# Shield_v1.net
KiCad netlist of a schematic drawn in EAGLE
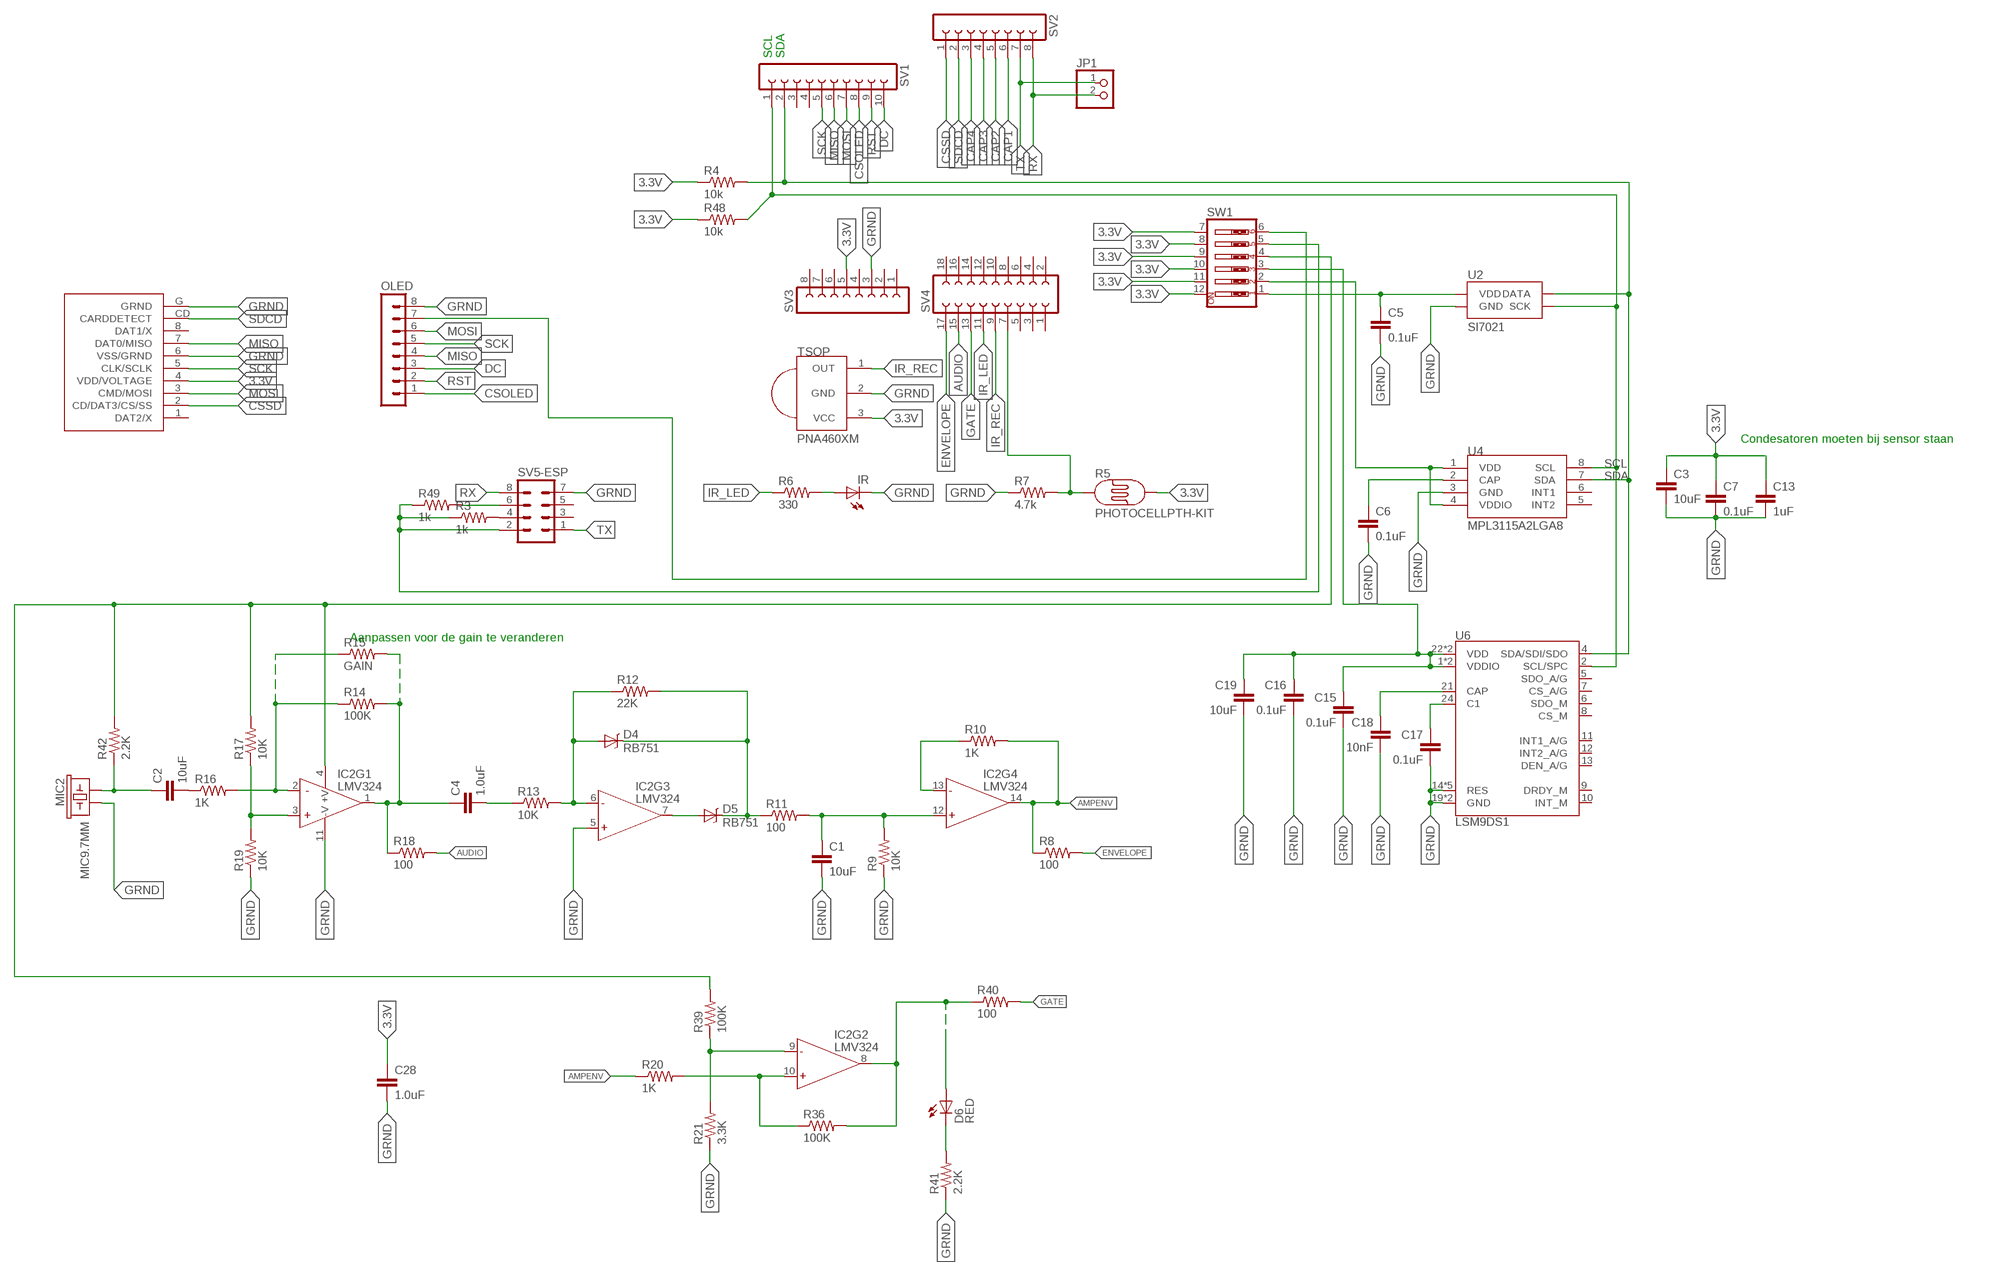
[diagram p0: schematic, sheet 1]

(export (version "E")
  (design (tool "Eeschema 10.0.6"))
  (components
    (comp (ref "C1")
      (value "10uF")
      (footprint "eagle-import:C1206")
      (libsource (lib "eagle-import") (part "C-EUC1206"))
    )
    (comp (ref "C2")
      (value "10uF")
      (footprint "eagle-import:C1206")
      (libsource (lib "eagle-import") (part "C-EUC1206"))
    )
    (comp (ref "C3")
      (value "10uF")
      (footprint "eagle-import:C1206")
      (libsource (lib "eagle-import") (part "C-EUC1206"))
    )
    (comp (ref "C4")
      (value "1.0uF")
      (footprint "eagle-import:C1206")
      (libsource (lib "eagle-import") (part "C-EUC1206"))
    )
    (comp (ref "C5")
      (value "0.1uF")
      (footprint "eagle-import:C1206")
      (libsource (lib "eagle-import") (part "C-EUC1206"))
    )
    (comp (ref "C6")
      (value "0.1uF")
      (footprint "eagle-import:C1206")
      (libsource (lib "eagle-import") (part "C-EUC1206"))
    )
    (comp (ref "C7")
      (value "0.1uF")
      (footprint "eagle-import:C1206")
      (libsource (lib "eagle-import") (part "C-EUC1206"))
    )
    (comp (ref "C13")
      (value "1uF")
      (footprint "eagle-import:C1206")
      (libsource (lib "eagle-import") (part "C-EUC1206"))
    )
    (comp (ref "C15")
      (value "0.1uF")
      (footprint "eagle-import:C1206")
      (libsource (lib "eagle-import") (part "C-EUC1206"))
    )
    (comp (ref "C16")
      (value "0.1uF")
      (footprint "eagle-import:C1206")
      (libsource (lib "eagle-import") (part "C-EUC1206"))
    )
    (comp (ref "C17")
      (value "0.1uF")
      (footprint "eagle-import:C1206")
      (libsource (lib "eagle-import") (part "C-EUC1206"))
    )
    (comp (ref "C18")
      (value "10nF")
      (footprint "eagle-import:C1206")
      (libsource (lib "eagle-import") (part "C-EUC1206"))
    )
    (comp (ref "C19")
      (value "10uF")
      (footprint "eagle-import:C1206")
      (libsource (lib "eagle-import") (part "C-EUC1206"))
    )
    (comp (ref "C28")
      (value "1.0uF")
      (footprint "eagle-import:C1206")
      (libsource (lib "eagle-import") (part "C-EUC1206"))
    )
    (comp (ref "D4")
      (value "RB751")
      (footprint "eagle-import:SOD-523")
      (libsource (lib "eagle-import") (part "RB751"))
    )
    (comp (ref "D5")
      (value "RB751")
      (footprint "eagle-import:SOD-523")
      (libsource (lib "eagle-import") (part "RB751"))
    )
    (comp (ref "D6")
      (value "RED")
      (footprint "eagle-import:LED3MM")
      (libsource (lib "eagle-import") (part "led_LED3MM"))
    )
    (comp (ref "IC2")
      (value "LMV324")
      (footprint "eagle-import:SO014")
      (libsource (lib "eagle-import") (part "LMV324"))
    )
    (comp (ref "IR")
      (value "LED5MM")
      (footprint "eagle-import:LED5MM")
      (libsource (lib "eagle-import") (part "LED5MM"))
    )
    (comp (ref "JP1")
      (value "PINHD-1X2")
      (footprint "eagle-import:1X02")
      (libsource (lib "eagle-import") (part "PINHD-1X2"))
    )
    (comp (ref "MIC2")
      (value "MIC9.7MM")
      (footprint "eagle-import:MIC-9.7MM")
      (libsource (lib "eagle-import") (part "MIC9.7MM"))
    )
    (comp (ref "OLED")
      (value "MA08-1")
      (footprint "eagle-import:MA08-1")
      (libsource (lib "eagle-import") (part "MA08-1"))
    )
    (comp (ref "R3")
      (value "1k")
      (footprint "eagle-import:R1206")
      (libsource (lib "eagle-import") (part "R-US_R1206"))
    )
    (comp (ref "R4")
      (value "10k")
      (footprint "eagle-import:R1206")
      (libsource (lib "eagle-import") (part "R-US_R1206"))
    )
    (comp (ref "R5")
      (value "PHOTOCELLPTH-KIT")
      (footprint "eagle-import:PHOTOCELL-KIT")
      (libsource (lib "eagle-import") (part "PHOTOCELLPTH-KIT"))
    )
    (comp (ref "R6")
      (value "330")
      (footprint "eagle-import:R1206")
      (libsource (lib "eagle-import") (part "R-US_R1206"))
    )
    (comp (ref "R7")
      (value "4.7k")
      (footprint "eagle-import:R1206")
      (libsource (lib "eagle-import") (part "R-US_R1206"))
    )
    (comp (ref "R8")
      (value "100")
      (footprint "eagle-import:R1206")
      (libsource (lib "eagle-import") (part "R-US_R1206"))
    )
    (comp (ref "R9")
      (value "10K")
      (footprint "eagle-import:R1206")
      (libsource (lib "eagle-import") (part "R-US_R1206"))
    )
    (comp (ref "R10")
      (value "1K")
      (footprint "eagle-import:R1206")
      (libsource (lib "eagle-import") (part "R-US_R1206"))
    )
    (comp (ref "R11")
      (value "100")
      (footprint "eagle-import:R1206")
      (libsource (lib "eagle-import") (part "R-US_R1206"))
    )
    (comp (ref "R12")
      (value "22K")
      (footprint "eagle-import:R1206")
      (libsource (lib "eagle-import") (part "R-US_R1206"))
    )
    (comp (ref "R13")
      (value "10K")
      (footprint "eagle-import:R1206")
      (libsource (lib "eagle-import") (part "R-US_R1206"))
    )
    (comp (ref "R14")
      (value "100K")
      (footprint "eagle-import:R1206")
      (libsource (lib "eagle-import") (part "R-US_R1206"))
    )
    (comp (ref "R15")
      (value "GAIN")
      (footprint "eagle-import:R1206")
      (libsource (lib "eagle-import") (part "R-US_R1206"))
    )
    (comp (ref "R16")
      (value "1K")
      (footprint "eagle-import:R1206")
      (libsource (lib "eagle-import") (part "R-US_R1206"))
    )
    (comp (ref "R17")
      (value "10K")
      (footprint "eagle-import:R1206")
      (libsource (lib "eagle-import") (part "R-US_R1206"))
    )
    (comp (ref "R18")
      (value "100")
      (footprint "eagle-import:R1206")
      (libsource (lib "eagle-import") (part "R-US_R1206"))
    )
    (comp (ref "R19")
      (value "10K")
      (footprint "eagle-import:R1206")
      (libsource (lib "eagle-import") (part "R-US_R1206"))
    )
    (comp (ref "R20")
      (value "1K")
      (footprint "eagle-import:R1206")
      (libsource (lib "eagle-import") (part "R-US_R1206"))
    )
    (comp (ref "R21")
      (value "3.3K")
      (footprint "eagle-import:R1206")
      (libsource (lib "eagle-import") (part "R-US_R1206"))
    )
    (comp (ref "R36")
      (value "100K")
      (footprint "eagle-import:R1206")
      (libsource (lib "eagle-import") (part "R-US_R1206"))
    )
    (comp (ref "R39")
      (value "100K")
      (footprint "eagle-import:R1206")
      (libsource (lib "eagle-import") (part "R-US_R1206"))
    )
    (comp (ref "R40")
      (value "100")
      (footprint "eagle-import:R1206")
      (libsource (lib "eagle-import") (part "R-US_R1206"))
    )
    (comp (ref "R41")
      (value "2.2K")
      (footprint "eagle-import:R1206")
      (libsource (lib "eagle-import") (part "R-US_R1206"))
    )
    (comp (ref "R42")
      (value "2.2K")
      (footprint "eagle-import:R1206")
      (libsource (lib "eagle-import") (part "R-US_R1206"))
    )
    (comp (ref "R48")
      (value "10k")
      (footprint "eagle-import:R1206")
      (libsource (lib "eagle-import") (part "R-US_R1206"))
    )
    (comp (ref "R49")
      (value "1k")
      (footprint "eagle-import:R1206")
      (libsource (lib "eagle-import") (part "R-US_R1206"))
    )
    (comp (ref "SV1")
      (value "FE10-1")
      (footprint "eagle-import:FE10")
      (libsource (lib "eagle-import") (part "FE10-1"))
    )
    (comp (ref "SV2")
      (value "FE08-1")
      (footprint "eagle-import:FE08")
      (libsource (lib "eagle-import") (part "FE08-1"))
    )
    (comp (ref "SV3")
      (value "FE08-1")
      (footprint "eagle-import:FE08")
      (libsource (lib "eagle-import") (part "FE08-1"))
    )
    (comp (ref "SV4")
      (value "FE09-2")
      (footprint "eagle-import:FE09-2")
      (libsource (lib "eagle-import") (part "FE09-2"))
    )
    (comp (ref "SV5-ESP")
      (value "MA04-2")
      (footprint "eagle-import:MA04-2")
      (libsource (lib "eagle-import") (part "MA04-2"))
    )
    (comp (ref "SW1")
      (value "SW_DIP-6")
      (footprint "eagle-import:EDG-06")
      (libsource (lib "eagle-import") (part "SW_DIP-6"))
    )
    (comp (ref "TSOP")
      (value "PNA460XM")
      (footprint "eagle-import:PNA460XM")
      (libsource (lib "eagle-import") (part "PNA460XM"))
    )
    (comp (ref "U$1")
      (value "SDCARD")
      (footprint "eagle-import:SD_CARD")
      (libsource (lib "eagle-import") (part "SDCARD"))
    )
    (comp (ref "U2")
      (value "SI7021")
      (footprint "eagle-import:SI7021")
      (libsource (lib "eagle-import") (part "SI7021"))
    )
    (comp (ref "U4")
      (value "MPL3115A2LGA8")
      (footprint "eagle-import:LGA8")
      (libsource (lib "eagle-import") (part "MPL3115A2LGA8"))
    )
    (comp (ref "U6")
      (value "LSM9DS1")
      (footprint "eagle-import:LGA24-8X4")
      (libsource (lib "eagle-import") (part "LSM9DS1"))
    )
  )
  (nets
    (net (code "1") (name "/SCL") (class "Default")
      (node (ref "R48") (pin "2") (pinfunction "2_2") (pintype "passive"))
      (node (ref "SV1") (pin "1") (pinfunction "1_1") (pintype "passive"))
      (node (ref "U2") (pin "SCK") (pinfunction "SCK_SCK") (pintype "input"))
      (node (ref "U4") (pin "8") (pinfunction "SCL_8") (pintype "bidirectional"))
      (node (ref "U6") (pin "2") (pinfunction "SCL/SPC_2") (pintype "bidirectional"))
    )
    (net (code "2") (name "/SDA") (class "Default")
      (node (ref "R4") (pin "2") (pinfunction "2_2") (pintype "passive"))
      (node (ref "SV1") (pin "2") (pinfunction "2_2") (pintype "passive"))
      (node (ref "U2") (pin "DATA") (pinfunction "DATA_DATA") (pintype "bidirectional"))
      (node (ref "U4") (pin "7") (pinfunction "SDA_7") (pintype "bidirectional"))
      (node (ref "U6") (pin "4") (pinfunction "SDA/SDI/SDO_4") (pintype "bidirectional"))
    )
    (net (code "3") (name "3.3V") (class "Default")
      (node (ref "C13") (pin "1") (pinfunction "1_1") (pintype "passive"))
      (node (ref "C28") (pin "1") (pinfunction "1_1") (pintype "passive"))
      (node (ref "C3") (pin "1") (pinfunction "1_1") (pintype "passive"))
      (node (ref "C7") (pin "1") (pinfunction "1_1") (pintype "passive"))
      (node (ref "R4") (pin "1") (pinfunction "1_1") (pintype "passive"))
      (node (ref "R48") (pin "1") (pinfunction "1_1") (pintype "passive"))
      (node (ref "R5") (pin "2") (pinfunction "P$2_2") (pintype "bidirectional"))
      (node (ref "SV3") (pin "5") (pinfunction "5_5") (pintype "passive"))
      (node (ref "SW1") (pin "10") (pinfunction "10_10") (pintype "passive"))
      (node (ref "SW1") (pin "11") (pinfunction "11_11") (pintype "passive"))
      (node (ref "SW1") (pin "12") (pinfunction "12_12") (pintype "passive"))
      (node (ref "SW1") (pin "7") (pinfunction "7_7") (pintype "passive"))
      (node (ref "SW1") (pin "8") (pinfunction "8_8") (pintype "passive"))
      (node (ref "SW1") (pin "9") (pinfunction "9_9") (pintype "passive"))
      (node (ref "TSOP") (pin "3") (pinfunction "VCC_3") (pintype "power_in"))
      (node (ref "U$1") (pin "4") (pinfunction "VDD/VOLTAGE_4") (pintype "bidirectional"))
    )
    (net (code "4") (name "AMPENV") (class "Default")
      (node (ref "IC2") (pin "14") (pinfunction "OUT_14") (pintype "output"))
      (node (ref "R10") (pin "2") (pinfunction "2_2") (pintype "passive"))
      (node (ref "R20") (pin "1") (pinfunction "1_1") (pintype "passive"))
      (node (ref "R8") (pin "1") (pinfunction "1_1") (pintype "passive"))
    )
    (net (code "5") (name "AUDIO") (class "Default")
      (node (ref "R18") (pin "2") (pinfunction "2_2") (pintype "passive"))
      (node (ref "R5") (pin "1") (pinfunction "P$1_1") (pintype "bidirectional"))
      (node (ref "R7") (pin "2") (pinfunction "2_2") (pintype "passive"))
      (node (ref "SV4") (pin "15") (pinfunction "15_15") (pintype "passive"))
      (node (ref "SV4") (pin "7") (pinfunction "7_7") (pintype "passive"))
    )
    (net (code "6") (name "CAP1") (class "Default")
      (node (ref "SV2") (pin "6") (pinfunction "6_6") (pintype "passive"))
    )
    (net (code "7") (name "CAP2") (class "Default")
      (node (ref "C18") (pin "1") (pinfunction "1_1") (pintype "passive"))
      (node (ref "SV2") (pin "5") (pinfunction "5_5") (pintype "passive"))
      (node (ref "U6") (pin "21") (pinfunction "CAP_21") (pintype "bidirectional"))
    )
    (net (code "8") (name "CAP3") (class "Default")
      (node (ref "SV2") (pin "4") (pinfunction "4_4") (pintype "passive"))
    )
    (net (code "9") (name "CAP4") (class "Default")
      (node (ref "SV2") (pin "3") (pinfunction "3_3") (pintype "passive"))
    )
    (net (code "10") (name "CSOLED") (class "Default")
      (node (ref "OLED") (pin "1") (pinfunction "1_1") (pintype "passive"))
      (node (ref "SV1") (pin "8") (pinfunction "8_8") (pintype "passive"))
    )
    (net (code "11") (name "CSSD") (class "Default")
      (node (ref "SV2") (pin "1") (pinfunction "1_1") (pintype "passive"))
      (node (ref "U$1") (pin "2") (pinfunction "CD/DAT3/CS/SS_2") (pintype "bidirectional"))
    )
    (net (code "12") (name "DC") (class "Default")
      (node (ref "OLED") (pin "3") (pinfunction "3_3") (pintype "passive"))
      (node (ref "SV1") (pin "10") (pinfunction "10_10") (pintype "passive"))
    )
    (net (code "13") (name "ENVELOPE") (class "Default")
      (node (ref "R8") (pin "2") (pinfunction "2_2") (pintype "passive"))
      (node (ref "SV4") (pin "17") (pinfunction "17_17") (pintype "passive"))
    )
    (net (code "14") (name "GATE") (class "Default")
      (node (ref "R40") (pin "2") (pinfunction "2_2") (pintype "passive"))
      (node (ref "SV4") (pin "13") (pinfunction "13_13") (pintype "passive"))
    )
    (net (code "15") (name "GRND") (class "Default")
      (node (ref "C1") (pin "2") (pinfunction "2_2") (pintype "passive"))
      (node (ref "C13") (pin "2") (pinfunction "2_2") (pintype "passive"))
      (node (ref "C15") (pin "2") (pinfunction "2_2") (pintype "passive"))
      (node (ref "C16") (pin "2") (pinfunction "2_2") (pintype "passive"))
      (node (ref "C17") (pin "2") (pinfunction "2_2") (pintype "passive"))
      (node (ref "C18") (pin "2") (pinfunction "2_2") (pintype "passive"))
      (node (ref "C19") (pin "2") (pinfunction "2_2") (pintype "passive"))
      (node (ref "C28") (pin "2") (pinfunction "2_2") (pintype "passive"))
      (node (ref "C3") (pin "2") (pinfunction "2_2") (pintype "passive"))
      (node (ref "C5") (pin "2") (pinfunction "2_2") (pintype "passive"))
      (node (ref "C6") (pin "2") (pinfunction "2_2") (pintype "passive"))
      (node (ref "C7") (pin "2") (pinfunction "2_2") (pintype "passive"))
      (node (ref "IC2") (pin "11") (pinfunction "-V_11") (pintype "power_in"))
      (node (ref "IC2") (pin "5") (pinfunction "+IN_5") (pintype "input"))
      (node (ref "IR") (pin "K") (pinfunction "C_K") (pintype "passive"))
      (node (ref "MIC2") (pin "2") (pinfunction "2_2") (pintype "passive"))
      (node (ref "OLED") (pin "8") (pinfunction "8_8") (pintype "passive"))
      (node (ref "R19") (pin "1") (pinfunction "1_1") (pintype "passive"))
      (node (ref "R21") (pin "1") (pinfunction "1_1") (pintype "passive"))
      (node (ref "R41") (pin "1") (pinfunction "1_1") (pintype "passive"))
      (node (ref "R7") (pin "1") (pinfunction "1_1") (pintype "passive"))
      (node (ref "R9") (pin "1") (pinfunction "1_1") (pintype "passive"))
      (node (ref "SV3") (pin "3") (pinfunction "3_3") (pintype "passive"))
      (node (ref "SV5-ESP") (pin "7") (pinfunction "7_7") (pintype "passive"))
      (node (ref "TSOP") (pin "2") (pinfunction "GND_2") (pintype "power_in"))
      (node (ref "U$1") (pin "6") (pinfunction "VSS/GRND_6") (pintype "bidirectional"))
      (node (ref "U$1") (pin "G") (pinfunction "GRND_G") (pintype "bidirectional"))
      (node (ref "U2") (pin "GND") (pinfunction "GND_GND") (pintype "power_in"))
      (node (ref "U4") (pin "3") (pinfunction "GND_3") (pintype "bidirectional"))
      (node (ref "U6") (pin "14") (pinfunction "RES_14") (pintype "bidirectional"))
      (node (ref "U6") (pin "15") (pinfunction "RES_15") (pintype "bidirectional"))
      (node (ref "U6") (pin "16") (pinfunction "RES_16") (pintype "bidirectional"))
      (node (ref "U6") (pin "17") (pinfunction "RES_17") (pintype "bidirectional"))
      (node (ref "U6") (pin "18") (pinfunction "RES_18") (pintype "bidirectional"))
      (node (ref "U6") (pin "19") (pinfunction "GND_19") (pintype "bidirectional"))
      (node (ref "U6") (pin "20") (pinfunction "GND_20") (pintype "bidirectional"))
    )
    (net (code "16") (name "IR_LED") (class "Default")
      (node (ref "R6") (pin "1") (pinfunction "1_1") (pintype "passive"))
      (node (ref "SV4") (pin "11") (pinfunction "11_11") (pintype "passive"))
    )
    (net (code "17") (name "IR_REC") (class "Default")
      (node (ref "SV4") (pin "9") (pinfunction "9_9") (pintype "passive"))
      (node (ref "TSOP") (pin "1") (pinfunction "OUT_1") (pintype "output"))
    )
    (net (code "18") (name "MISO") (class "Default")
      (node (ref "OLED") (pin "4") (pinfunction "4_4") (pintype "passive"))
      (node (ref "SV1") (pin "6") (pinfunction "6_6") (pintype "passive"))
      (node (ref "U$1") (pin "7") (pinfunction "DAT0/MISO_7") (pintype "bidirectional"))
    )
    (net (code "19") (name "MOSI") (class "Default")
      (node (ref "OLED") (pin "6") (pinfunction "6_6") (pintype "passive"))
      (node (ref "SV1") (pin "7") (pinfunction "7_7") (pintype "passive"))
      (node (ref "U$1") (pin "3") (pinfunction "CMD/MOSI_3") (pintype "bidirectional"))
    )
    (net (code "20") (name "Net-(C2-Pad1)") (class "Default")
      (node (ref "C2") (pin "1") (pinfunction "1_1") (pintype "passive"))
      (node (ref "MIC2") (pin "1") (pinfunction "1_1") (pintype "passive"))
      (node (ref "R42") (pin "1") (pinfunction "1_1") (pintype "passive"))
    )
    (net (code "21") (name "Net-(C2-Pad2)") (class "Default")
      (node (ref "C2") (pin "2") (pinfunction "2_2") (pintype "passive"))
      (node (ref "R16") (pin "1") (pinfunction "1_1") (pintype "passive"))
    )
    (net (code "22") (name "Net-(C4-Pad2)") (class "Default")
      (node (ref "C4") (pin "2") (pinfunction "2_2") (pintype "passive"))
      (node (ref "R13") (pin "1") (pinfunction "1_1") (pintype "passive"))
    )
    (net (code "23") (name "Net-(C5-Pad1)") (class "Default")
      (node (ref "C5") (pin "1") (pinfunction "1_1") (pintype "passive"))
      (node (ref "SW1") (pin "1") (pinfunction "1_1") (pintype "passive"))
      (node (ref "U2") (pin "VDD") (pinfunction "VDD_VDD") (pintype "power_in"))
    )
    (net (code "24") (name "Net-(C15-Pad1)") (class "Default")
      (node (ref "C15") (pin "1") (pinfunction "1_1") (pintype "passive"))
      (node (ref "C16") (pin "1") (pinfunction "1_1") (pintype "passive"))
      (node (ref "C19") (pin "1") (pinfunction "1_1") (pintype "passive"))
      (node (ref "SW1") (pin "3") (pinfunction "3_3") (pintype "passive"))
      (node (ref "U6") (pin "1") (pinfunction "VDDIO_1") (pintype "bidirectional"))
      (node (ref "U6") (pin "22") (pinfunction "VDD_22") (pintype "bidirectional"))
      (node (ref "U6") (pin "23") (pinfunction "VDD_23") (pintype "bidirectional"))
      (node (ref "U6") (pin "3") (pinfunction "VDDIO_3") (pintype "bidirectional"))
    )
    (net (code "25") (name "Net-(D4-PadC)") (class "Default")
      (node (ref "D4") (pin "C") (pinfunction "C_C") (pintype "passive"))
      (node (ref "D5") (pin "C") (pinfunction "C_C") (pintype "passive"))
      (node (ref "R11") (pin "1") (pinfunction "1_1") (pintype "passive"))
      (node (ref "R12") (pin "2") (pinfunction "2_2") (pintype "passive"))
    )
    (net (code "26") (name "Net-(D6-C)") (class "Default")
      (node (ref "D6") (pin "K") (pinfunction "C_K") (pintype "passive"))
      (node (ref "R41") (pin "2") (pinfunction "2_2") (pintype "passive"))
    )
    (net (code "27") (name "Net-(IC2A-+IN)") (class "Default")
      (node (ref "IC2") (pin "3") (pinfunction "+IN_3") (pintype "input"))
      (node (ref "R17") (pin "1") (pinfunction "1_1") (pintype "passive"))
      (node (ref "R19") (pin "2") (pinfunction "2_2") (pintype "passive"))
    )
    (net (code "28") (name "Net-(IC2A-+V)") (class "Default")
      (node (ref "IC2") (pin "4") (pinfunction "+V_4") (pintype "power_in"))
      (node (ref "R17") (pin "2") (pinfunction "2_2") (pintype "passive"))
      (node (ref "R39") (pin "2") (pinfunction "2_2") (pintype "passive"))
      (node (ref "R42") (pin "2") (pinfunction "2_2") (pintype "passive"))
      (node (ref "SW1") (pin "4") (pinfunction "4_4") (pintype "passive"))
    )
    (net (code "29") (name "Net-(IC2A--IN)") (class "Default")
      (node (ref "IC2") (pin "2") (pinfunction "-IN_2") (pintype "input"))
      (node (ref "R14") (pin "1") (pinfunction "1_1") (pintype "passive"))
      (node (ref "R15") (pin "1") (pinfunction "1_1") (pintype "passive"))
      (node (ref "R16") (pin "2") (pinfunction "2_2") (pintype "passive"))
    )
    (net (code "30") (name "Net-(IC2A-OUT)") (class "Default")
      (node (ref "C4") (pin "1") (pinfunction "1_1") (pintype "passive"))
      (node (ref "IC2") (pin "1") (pinfunction "OUT_1") (pintype "output"))
      (node (ref "R14") (pin "2") (pinfunction "2_2") (pintype "passive"))
      (node (ref "R15") (pin "2") (pinfunction "2_2") (pintype "passive"))
      (node (ref "R18") (pin "1") (pinfunction "1_1") (pintype "passive"))
    )
    (net (code "31") (name "Net-(IC2B-+IN)") (class "Default")
      (node (ref "IC2") (pin "10") (pinfunction "+IN_10") (pintype "input"))
      (node (ref "R20") (pin "2") (pinfunction "2_2") (pintype "passive"))
      (node (ref "R36") (pin "1") (pinfunction "1_1") (pintype "passive"))
    )
    (net (code "32") (name "Net-(IC2B--IN)") (class "Default")
      (node (ref "IC2") (pin "9") (pinfunction "-IN_9") (pintype "input"))
      (node (ref "R21") (pin "2") (pinfunction "2_2") (pintype "passive"))
      (node (ref "R39") (pin "1") (pinfunction "1_1") (pintype "passive"))
    )
    (net (code "33") (name "Net-(IC2B-OUT)") (class "Default")
      (node (ref "D6") (pin "A") (pinfunction "A_A") (pintype "passive"))
      (node (ref "IC2") (pin "8") (pinfunction "OUT_8") (pintype "output"))
      (node (ref "R36") (pin "2") (pinfunction "2_2") (pintype "passive"))
      (node (ref "R40") (pin "1") (pinfunction "1_1") (pintype "passive"))
    )
    (net (code "34") (name "Net-(IC2C--IN)") (class "Default")
      (node (ref "D4") (pin "A") (pinfunction "A_A") (pintype "passive"))
      (node (ref "IC2") (pin "6") (pinfunction "-IN_6") (pintype "input"))
      (node (ref "R12") (pin "1") (pinfunction "1_1") (pintype "passive"))
      (node (ref "R13") (pin "2") (pinfunction "2_2") (pintype "passive"))
    )
    (net (code "35") (name "Net-(IC2C-OUT)") (class "Default")
      (node (ref "D5") (pin "A") (pinfunction "A_A") (pintype "passive"))
      (node (ref "IC2") (pin "7") (pinfunction "OUT_7") (pintype "output"))
    )
    (net (code "36") (name "Net-(IC2D-+IN)") (class "Default")
      (node (ref "C1") (pin "1") (pinfunction "1_1") (pintype "passive"))
      (node (ref "IC2") (pin "12") (pinfunction "+IN_12") (pintype "input"))
      (node (ref "R11") (pin "2") (pinfunction "2_2") (pintype "passive"))
      (node (ref "R9") (pin "2") (pinfunction "2_2") (pintype "passive"))
    )
    (net (code "37") (name "Net-(IC2D--IN)") (class "Default")
      (node (ref "IC2") (pin "13") (pinfunction "-IN_13") (pintype "input"))
      (node (ref "R10") (pin "1") (pinfunction "1_1") (pintype "passive"))
    )
    (net (code "38") (name "Net-(IR-PadA)") (class "Default")
      (node (ref "IR") (pin "A") (pinfunction "A_A") (pintype "passive"))
      (node (ref "R6") (pin "2") (pinfunction "2_2") (pintype "passive"))
    )
    (net (code "39") (name "Net-(OLED-Pad7)") (class "Default")
      (node (ref "OLED") (pin "7") (pinfunction "7_7") (pintype "passive"))
      (node (ref "SW1") (pin "6") (pinfunction "6_6") (pintype "passive"))
    )
    (net (code "40") (name "Net-(R3-Pad1)") (class "Default")
      (node (ref "R3") (pin "1") (pinfunction "1_1") (pintype "passive"))
      (node (ref "R49") (pin "1") (pinfunction "1_1") (pintype "passive"))
      (node (ref "SV5-ESP") (pin "2") (pinfunction "2_2") (pintype "passive"))
      (node (ref "SW1") (pin "5") (pinfunction "5_5") (pintype "passive"))
    )
    (net (code "41") (name "Net-(R3-Pad2)") (class "Default")
      (node (ref "R3") (pin "2") (pinfunction "2_2") (pintype "passive"))
      (node (ref "SV5-ESP") (pin "4") (pinfunction "4_4") (pintype "passive"))
    )
    (net (code "42") (name "Net-(R49-Pad2)") (class "Default")
      (node (ref "R49") (pin "2") (pinfunction "2_2") (pintype "passive"))
      (node (ref "SV5-ESP") (pin "6") (pinfunction "6_6") (pintype "passive"))
    )
    (net (code "43") (name "Net-(U4-CAP)") (class "Default")
      (node (ref "C6") (pin "1") (pinfunction "1_1") (pintype "passive"))
      (node (ref "U4") (pin "2") (pinfunction "CAP_2") (pintype "bidirectional"))
    )
    (net (code "44") (name "Net-(U4-VDD)") (class "Default")
      (node (ref "SW1") (pin "2") (pinfunction "2_2") (pintype "passive"))
      (node (ref "U4") (pin "1") (pinfunction "VDD_1") (pintype "bidirectional"))
      (node (ref "U4") (pin "4") (pinfunction "VDDIO_4") (pintype "bidirectional"))
    )
    (net (code "45") (name "Net-(U6-C1)") (class "Default")
      (node (ref "C17") (pin "1") (pinfunction "1_1") (pintype "passive"))
      (node (ref "U6") (pin "24") (pinfunction "C1_24") (pintype "bidirectional"))
    )
    (net (code "46") (name "RST") (class "Default")
      (node (ref "OLED") (pin "2") (pinfunction "2_2") (pintype "passive"))
      (node (ref "SV1") (pin "9") (pinfunction "9_9") (pintype "passive"))
    )
    (net (code "47") (name "RX") (class "Default")
      (node (ref "JP1") (pin "2") (pinfunction "2_2") (pintype "passive"))
      (node (ref "SV2") (pin "8") (pinfunction "8_8") (pintype "passive"))
      (node (ref "SV5-ESP") (pin "8") (pinfunction "8_8") (pintype "passive"))
    )
    (net (code "48") (name "SCK") (class "Default")
      (node (ref "OLED") (pin "5") (pinfunction "5_5") (pintype "passive"))
      (node (ref "SV1") (pin "5") (pinfunction "5_5") (pintype "passive"))
      (node (ref "U$1") (pin "5") (pinfunction "CLK/SCLK_5") (pintype "bidirectional"))
    )
    (net (code "49") (name "SDCD") (class "Default")
      (node (ref "SV2") (pin "2") (pinfunction "2_2") (pintype "passive"))
      (node (ref "U$1") (pin "CD") (pinfunction "CARDDETECT_CD") (pintype "bidirectional"))
    )
    (net (code "50") (name "TX") (class "Default")
      (node (ref "JP1") (pin "1") (pinfunction "1_1") (pintype "passive"))
      (node (ref "SV2") (pin "7") (pinfunction "7_7") (pintype "passive"))
      (node (ref "SV5-ESP") (pin "1") (pinfunction "1_1") (pintype "passive"))
    )
    (net (code "51") (name "unconnected-(SV1-Pad3)") (class "Default")
      (node (ref "SV1") (pin "3") (pinfunction "3_3") (pintype "passive"))
    )
    (net (code "52") (name "unconnected-(SV1-Pad4)") (class "Default")
      (node (ref "SV1") (pin "4") (pinfunction "4_4") (pintype "passive"))
    )
    (net (code "53") (name "unconnected-(SV3-Pad1)") (class "Default")
      (node (ref "SV3") (pin "1") (pinfunction "1_1") (pintype "passive"))
    )
    (net (code "54") (name "unconnected-(SV3-Pad2)") (class "Default")
      (node (ref "SV3") (pin "2") (pinfunction "2_2") (pintype "passive"))
    )
    (net (code "55") (name "unconnected-(SV3-Pad4)") (class "Default")
      (node (ref "SV3") (pin "4") (pinfunction "4_4") (pintype "passive"))
    )
    (net (code "56") (name "unconnected-(SV3-Pad6)") (class "Default")
      (node (ref "SV3") (pin "6") (pinfunction "6_6") (pintype "passive"))
    )
    (net (code "57") (name "unconnected-(SV3-Pad7)") (class "Default")
      (node (ref "SV3") (pin "7") (pinfunction "7_7") (pintype "passive"))
    )
    (net (code "58") (name "unconnected-(SV3-Pad8)") (class "Default")
      (node (ref "SV3") (pin "8") (pinfunction "8_8") (pintype "passive"))
    )
    (net (code "59") (name "unconnected-(SV4-Pad1)") (class "Default")
      (node (ref "SV4") (pin "1") (pinfunction "1_1") (pintype "passive"))
    )
    (net (code "60") (name "unconnected-(SV4-Pad2)") (class "Default")
      (node (ref "SV4") (pin "2") (pinfunction "2_2") (pintype "passive"))
    )
    (net (code "61") (name "unconnected-(SV4-Pad3)") (class "Default")
      (node (ref "SV4") (pin "3") (pinfunction "3_3") (pintype "passive"))
    )
    (net (code "62") (name "unconnected-(SV4-Pad4)") (class "Default")
      (node (ref "SV4") (pin "4") (pinfunction "4_4") (pintype "passive"))
    )
    (net (code "63") (name "unconnected-(SV4-Pad5)") (class "Default")
      (node (ref "SV4") (pin "5") (pinfunction "5_5") (pintype "passive"))
    )
    (net (code "64") (name "unconnected-(SV4-Pad6)") (class "Default")
      (node (ref "SV4") (pin "6") (pinfunction "6_6") (pintype "passive"))
    )
    (net (code "65") (name "unconnected-(SV4-Pad8)") (class "Default")
      (node (ref "SV4") (pin "8") (pinfunction "8_8") (pintype "passive"))
    )
    (net (code "66") (name "unconnected-(SV4-Pad10)") (class "Default")
      (node (ref "SV4") (pin "10") (pinfunction "10_10") (pintype "passive"))
    )
    (net (code "67") (name "unconnected-(SV4-Pad12)") (class "Default")
      (node (ref "SV4") (pin "12") (pinfunction "12_12") (pintype "passive"))
    )
    (net (code "68") (name "unconnected-(SV4-Pad14)") (class "Default")
      (node (ref "SV4") (pin "14") (pinfunction "14_14") (pintype "passive"))
    )
    (net (code "69") (name "unconnected-(SV4-Pad16)") (class "Default")
      (node (ref "SV4") (pin "16") (pinfunction "16_16") (pintype "passive"))
    )
    (net (code "70") (name "unconnected-(SV4-Pad18)") (class "Default")
      (node (ref "SV4") (pin "18") (pinfunction "18_18") (pintype "passive"))
    )
    (net (code "71") (name "unconnected-(SV5-ESP-Pad3)") (class "Default")
      (node (ref "SV5-ESP") (pin "3") (pinfunction "3_3") (pintype "passive"))
    )
    (net (code "72") (name "unconnected-(SV5-ESP-Pad5)") (class "Default")
      (node (ref "SV5-ESP") (pin "5") (pinfunction "5_5") (pintype "passive"))
    )
    (net (code "73") (name "unconnected-(U$1-DAT1{slash}X-Pad8)") (class "Default")
      (node (ref "U$1") (pin "8") (pinfunction "DAT1/X_8") (pintype "bidirectional"))
    )
    (net (code "74") (name "unconnected-(U$1-DAT2{slash}X-Pad1)") (class "Default")
      (node (ref "U$1") (pin "1") (pinfunction "DAT2/X_1") (pintype "bidirectional"))
    )
    (net (code "75") (name "unconnected-(U4-INT1-Pad6)") (class "Default")
      (node (ref "U4") (pin "6") (pinfunction "INT1_6") (pintype "bidirectional"))
    )
    (net (code "76") (name "unconnected-(U4-INT2-Pad5)") (class "Default")
      (node (ref "U4") (pin "5") (pinfunction "INT2_5") (pintype "bidirectional"))
    )
    (net (code "77") (name "unconnected-(U6-CS_A{slash}G-Pad7)") (class "Default")
      (node (ref "U6") (pin "7") (pinfunction "CS_A/G_7") (pintype "bidirectional"))
    )
    (net (code "78") (name "unconnected-(U6-CS_M-Pad8)") (class "Default")
      (node (ref "U6") (pin "8") (pinfunction "CS_M_8") (pintype "bidirectional"))
    )
    (net (code "79") (name "unconnected-(U6-DEN_A{slash}G-Pad13)") (class "Default")
      (node (ref "U6") (pin "13") (pinfunction "DEN_A/G_13") (pintype "bidirectional"))
    )
    (net (code "80") (name "unconnected-(U6-DRDY_M-Pad9)") (class "Default")
      (node (ref "U6") (pin "9") (pinfunction "DRDY_M_9") (pintype "bidirectional"))
    )
    (net (code "81") (name "unconnected-(U6-INT1_A{slash}G-Pad11)") (class "Default")
      (node (ref "U6") (pin "11") (pinfunction "INT1_A/G_11") (pintype "bidirectional"))
    )
    (net (code "82") (name "unconnected-(U6-INT2_A{slash}G-Pad12)") (class "Default")
      (node (ref "U6") (pin "12") (pinfunction "INT2_A/G_12") (pintype "bidirectional"))
    )
    (net (code "83") (name "unconnected-(U6-INT_M-Pad10)") (class "Default")
      (node (ref "U6") (pin "10") (pinfunction "INT_M_10") (pintype "bidirectional"))
    )
    (net (code "84") (name "unconnected-(U6-SDO_A{slash}G-Pad5)") (class "Default")
      (node (ref "U6") (pin "5") (pinfunction "SDO_A/G_5") (pintype "bidirectional"))
    )
    (net (code "85") (name "unconnected-(U6-SDO_M-Pad6)") (class "Default")
      (node (ref "U6") (pin "6") (pinfunction "SDO_M_6") (pintype "bidirectional"))
    )
  )
)
